# Arduino_SLVN.net
KiCad netlist of a schematic drawn in Altium Designer
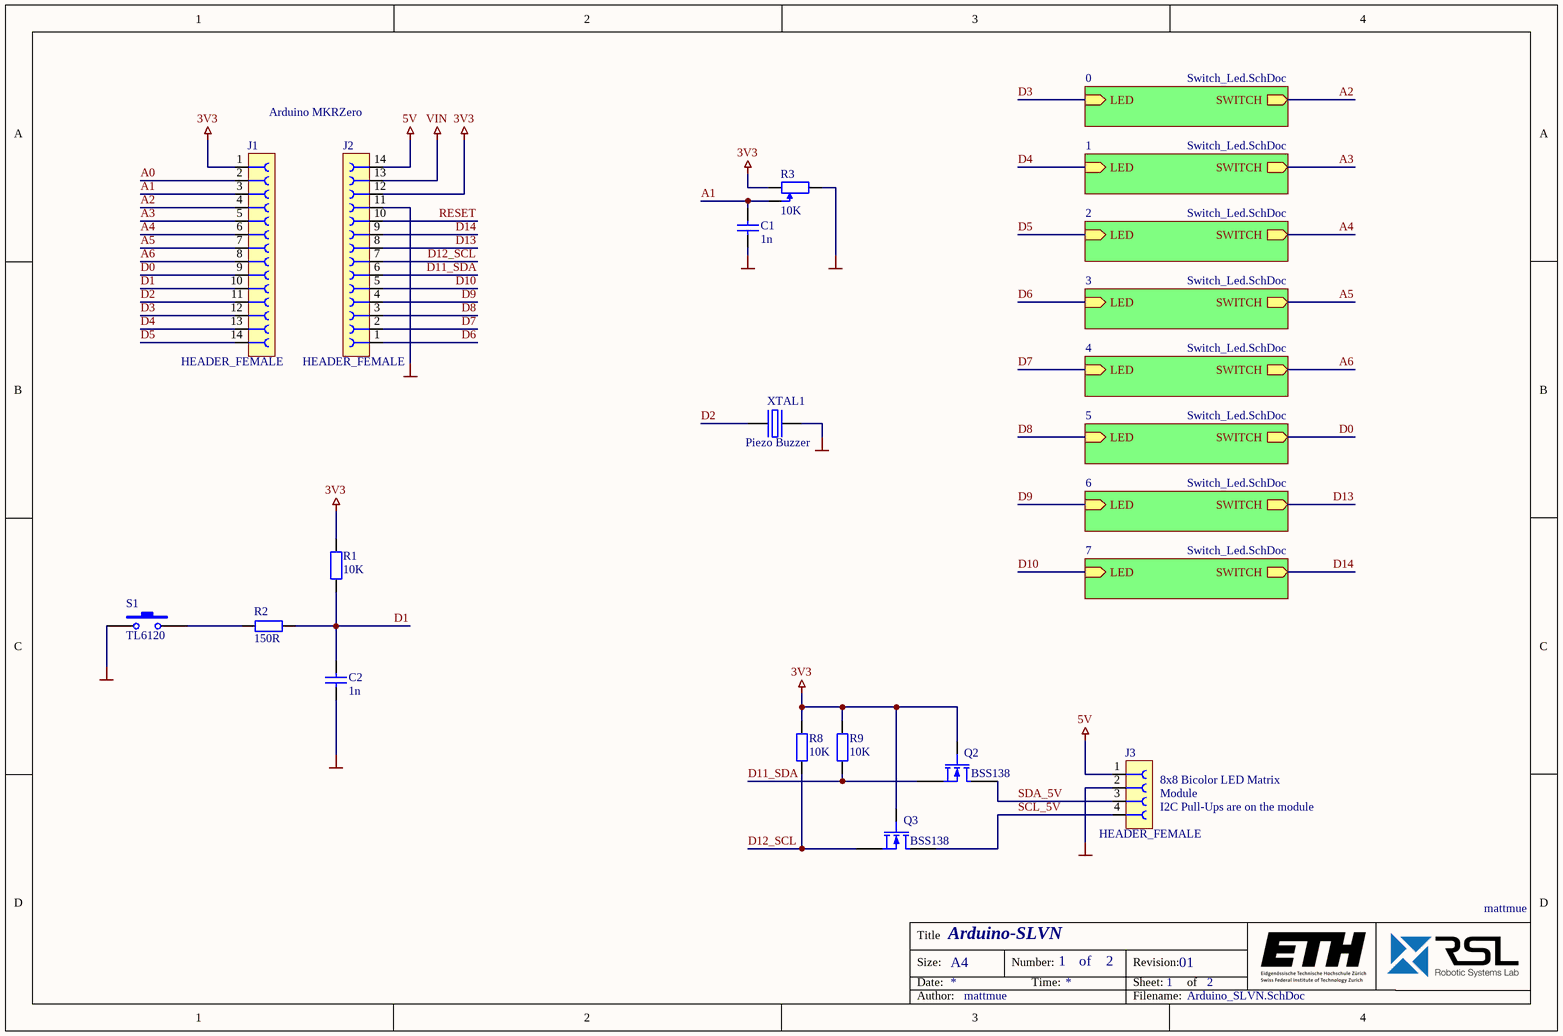
[diagram p0: Arduino_SLVN.SchDoc]

(export (version "E")
  (design (tool "Eeschema 10.0.6"))
  (components
    (comp (ref "C1")
      (value "1n")
      (footprint "SMD_CAPC1608X08N")
      (description "CERCAP 1n 100V 1% NP0/C0G 0603")
      (fields
        (field (name "MANUFACTURER") "KEMET")
        (field (name "MANUFACTURER PART NUMBER") "C0603C102F1GAC7867")
      )
      (libsource (lib "ETHZ Vault") (part "Cap"))
    )
    (comp (ref "C2")
      (value "1n")
      (footprint "SMD_CAPC1608X08N")
      (description "CERCAP 1n 100V 1% NP0/C0G 0603")
      (fields
        (field (name "MANUFACTURER") "KEMET")
        (field (name "MANUFACTURER PART NUMBER") "C0603C102F1GAC7867")
      )
      (libsource (lib "ETHZ Vault") (part "Cap"))
    )
    (comp (ref "J1")
      (value "HEADER_FEMALE")
      (footprint "THT_CONN_1x14_FEMALE_2.54")
      (description "CONN Female 1x14 2.54mm Straight THT 2.54x35.6mm")
      (fields
        (field (name "MANUFACTURER") "Sullins Connector Solutions")
        (field (name "MANUFACTURER PART NUMBER") "PPTC141LFBN-RC")
      )
      (libsource (lib "ETHZ Vault") (part "CON 14x1 Female"))
    )
    (comp (ref "J2")
      (value "HEADER_FEMALE")
      (footprint "THT_CONN_1x14_FEMALE_2.54")
      (description "CONN Female 1x14 2.54mm Straight THT 2.54x35.6mm")
      (fields
        (field (name "MANUFACTURER") "Sullins Connector Solutions")
        (field (name "MANUFACTURER PART NUMBER") "PPTC141LFBN-RC")
      )
      (libsource (lib "") (part "CON 14x1 Female_1"))
    )
    (comp (ref "J3")
      (value "HEADER_FEMALE")
      (footprint "THT_CONN_1x4_FEMALE_2.54")
      (description "CONN Female 1x4 2.54mm Straight THT 2.54x10.16mm")
      (fields
        (field (name "MANUFACTURER") "Sullins Connector Solutions")
        (field (name "MANUFACTURER PART NUMBER") "PPTC041LFBN-RC")
      )
      (libsource (lib "ETHZ Vault") (part "CON 4x1 Female"))
    )
    (comp (ref "Q2")
      (value "BSS138")
      (footprint "SOT323 SC70")
      (description "MOSFET N 0.2A 50V SOT323")
      (fields
        (field (name "MANUFACTURER2 PART NUMBER") "BSS138W-TP")
        (field (name "MANUFACTURER") "Diodes Incorporated")
      )
      (libsource (lib "ETHZ Vault") (part "MOSFET-N"))
    )
    (comp (ref "Q3")
      (value "BSS138")
      (footprint "SOT323 SC70")
      (description "MOSFET N 0.2A 50V SOT323")
      (fields
        (field (name "MANUFACTURER2 PART NUMBER") "BSS138W-TP")
        (field (name "MANUFACTURER") "Diodes Incorporated")
      )
      (libsource (lib "ETHZ Vault") (part "MOSFET-N"))
    )
    (comp (ref "R1")
      (value "10K")
      (footprint "SMD_RESC1608X05N")
      (description "RES 10K 100mW 1% 0603")
      (fields
        (field (name "MANUFACTURER") "YAEGO")
        (field (name "MANUFACTURER PART NUMBER") "RC0603FR-0710KL")
      )
      (libsource (lib "ETHZ Vault") (part "Res"))
    )
    (comp (ref "R2")
      (value "150R")
      (footprint "SMD_RESC1608X05N")
      (description "RES 150R 100mW 1% 0603")
      (fields
        (field (name "MANUFACTURER") "YAEGO")
        (field (name "MANUFACTURER PART NUMBER") "RC0603FR-07150RL")
      )
      (libsource (lib "ETHZ Vault") (part "Res"))
    )
    (comp (ref "R3")
      (value "10K")
      (footprint "THT_PTV09A-1")
      (description "POTENTIOMETER 10K 50mW 20% 11x9.7mm")
      (fields
        (field (name "MANUFACTURER") "Bourns Inc.")
        (field (name "MANUFACTURER PART NUMBER") "PTV09A-4020S-B103")
      )
      (libsource (lib "ETHZ Vault") (part "Res poti"))
    )
    (comp (ref "R8")
      (value "10K")
      (footprint "SMD_RESC1608X05N")
      (description "RES 10K 100mW 1% 0603")
      (fields
        (field (name "MANUFACTURER") "YAEGO")
        (field (name "MANUFACTURER PART NUMBER") "RC0603FR-0710KL")
      )
      (libsource (lib "ETHZ Vault") (part "Res"))
    )
    (comp (ref "R9")
      (value "10K")
      (footprint "SMD_RESC1608X05N")
      (description "RES 10K 100mW 1% 0603")
      (fields
        (field (name "MANUFACTURER") "YAEGO")
        (field (name "MANUFACTURER PART NUMBER") "RC0603FR-0710KL")
      )
      (libsource (lib "ETHZ Vault") (part "Res"))
    )
    (comp (ref "S1")
      (value "TL6120")
      (footprint "SMD_TL6120")
      (description "BUTTON SPST 12V 0.05A 7.4x7.4mm")
      (fields
        (field (name "MANUFACTURER") "E-Switch")
        (field (name "MANUFACTURER PART NUMBER") "TL6120CF300QG")
      )
      (libsource (lib "ETHZ Vault") (part "SW PB"))
    )
    (comp (ref "sdfg1")
      (value "Mattmue-Logo")
      (footprint "GRAPH_MATTMUE_6MM")
      (description "GRAPH MATTMUE")
      (libsource (lib "ETHZ Vault") (part "Mattmue"))
    )
    (comp (ref "XTAL1")
      (value "PS1240P02BT")
      (footprint "THT_PIEZO_5mm")
      (description "PASSIVE PIEZO_BUZZER 12.6x7.8mm")
      (fields (field (name "MANUFACTURER") "TDK Corporation") (field (name "NOTE") "Piezo Buzzer"))
      (libsource (lib "ETHZ Vault") (part "XTAL_2P"))
    )
  )
  (nets
    (net (code "1") (name "/A0") (class "Default")
      (node (ref "J1") (pin "2") (pinfunction "2_2") (pintype "passive"))
    )
    (net (code "2") (name "/A1") (class "Default")
      (node (ref "C1") (pin "2") (pinfunction "2_2") (pintype "passive"))
      (node (ref "J1") (pin "3") (pinfunction "3_3") (pintype "passive"))
      (node (ref "R3") (pin "3") (pinfunction "TAP_3") (pintype "passive"))
    )
    (net (code "3") (name "/A2") (class "Default")
      (node (ref "J1") (pin "4") (pinfunction "4_4") (pintype "passive"))
    )
    (net (code "4") (name "/A3") (class "Default")
      (node (ref "J1") (pin "5") (pinfunction "5_5") (pintype "passive"))
    )
    (net (code "5") (name "/A4") (class "Default")
      (node (ref "J1") (pin "6") (pinfunction "6_6") (pintype "passive"))
    )
    (net (code "6") (name "/A5") (class "Default")
      (node (ref "J1") (pin "7") (pinfunction "7_7") (pintype "passive"))
    )
    (net (code "7") (name "/A6") (class "Default")
      (node (ref "J1") (pin "8") (pinfunction "8_8") (pintype "passive"))
    )
    (net (code "8") (name "/D0") (class "Default")
      (node (ref "J1") (pin "9") (pinfunction "9_9") (pintype "passive"))
    )
    (net (code "9") (name "/D1") (class "Default")
      (node (ref "C2") (pin "2") (pinfunction "2_2") (pintype "passive"))
      (node (ref "J1") (pin "10") (pinfunction "10_10") (pintype "passive"))
      (node (ref "R1") (pin "1") (pinfunction "1_1") (pintype "passive"))
      (node (ref "R2") (pin "1") (pinfunction "1_1") (pintype "passive"))
    )
    (net (code "10") (name "/D2") (class "Default")
      (node (ref "J1") (pin "11") (pinfunction "11_11") (pintype "passive"))
      (node (ref "XTAL1") (pin "1") (pinfunction "1_1") (pintype "passive"))
    )
    (net (code "11") (name "/D3") (class "Default")
      (node (ref "J1") (pin "12") (pinfunction "12_12") (pintype "passive"))
    )
    (net (code "12") (name "/D4") (class "Default")
      (node (ref "J1") (pin "13") (pinfunction "13_13") (pintype "passive"))
    )
    (net (code "13") (name "/D5") (class "Default")
      (node (ref "J1") (pin "14") (pinfunction "14_14") (pintype "passive"))
    )
    (net (code "14") (name "/D6") (class "Default")
      (node (ref "J2") (pin "1") (pinfunction "1_1") (pintype "passive"))
    )
    (net (code "15") (name "/D7") (class "Default")
      (node (ref "J2") (pin "2") (pinfunction "2_2") (pintype "passive"))
    )
    (net (code "16") (name "/D8") (class "Default")
      (node (ref "J2") (pin "3") (pinfunction "3_3") (pintype "passive"))
    )
    (net (code "17") (name "/D9") (class "Default")
      (node (ref "J2") (pin "4") (pinfunction "4_4") (pintype "passive"))
    )
    (net (code "18") (name "/D10") (class "Default")
      (node (ref "J2") (pin "5") (pinfunction "5_5") (pintype "passive"))
    )
    (net (code "19") (name "/D11_SDA") (class "Default")
      (node (ref "J2") (pin "6") (pinfunction "6_6") (pintype "passive"))
      (node (ref "Q2") (pin "2") (pinfunction "S_2") (pintype "passive"))
      (node (ref "R9") (pin "1") (pinfunction "1_1") (pintype "passive"))
    )
    (net (code "20") (name "/D12_SCL") (class "Default")
      (node (ref "J2") (pin "7") (pinfunction "7_7") (pintype "passive"))
      (node (ref "Q3") (pin "2") (pinfunction "S_2") (pintype "passive"))
      (node (ref "R8") (pin "1") (pinfunction "1_1") (pintype "passive"))
    )
    (net (code "21") (name "/D13") (class "Default")
      (node (ref "J2") (pin "8") (pinfunction "8_8") (pintype "passive"))
    )
    (net (code "22") (name "/D14") (class "Default")
      (node (ref "J2") (pin "9") (pinfunction "9_9") (pintype "passive"))
    )
    (net (code "23") (name "/RESET") (class "Default")
      (node (ref "J2") (pin "10") (pinfunction "10_10") (pintype "passive"))
    )
    (net (code "24") (name "/SCL_5V") (class "Default")
      (node (ref "J3") (pin "4") (pinfunction "4_4") (pintype "passive"))
      (node (ref "Q3") (pin "3") (pinfunction "D_3") (pintype "passive"))
    )
    (net (code "25") (name "/SDA_5V") (class "Default")
      (node (ref "J3") (pin "3") (pinfunction "3_3") (pintype "passive"))
      (node (ref "Q2") (pin "3") (pinfunction "D_3") (pintype "passive"))
    )
    (net (code "26") (name "3V3") (class "Default")
      (node (ref "J1") (pin "1") (pinfunction "1_1") (pintype "passive"))
      (node (ref "J2") (pin "12") (pinfunction "12_12") (pintype "passive"))
      (node (ref "Q2") (pin "1") (pinfunction "G_1") (pintype "passive"))
      (node (ref "Q3") (pin "1") (pinfunction "G_1") (pintype "passive"))
      (node (ref "R1") (pin "2") (pinfunction "2_2") (pintype "passive"))
      (node (ref "R3") (pin "1") (pinfunction "1_1") (pintype "passive"))
      (node (ref "R8") (pin "2") (pinfunction "2_2") (pintype "passive"))
      (node (ref "R9") (pin "2") (pinfunction "2_2") (pintype "passive"))
    )
    (net (code "27") (name "5V") (class "Default")
      (node (ref "J2") (pin "14") (pinfunction "14_14") (pintype "passive"))
      (node (ref "J3") (pin "1") (pinfunction "1_1") (pintype "passive"))
    )
    (net (code "28") (name "GND") (class "Default")
      (node (ref "C1") (pin "1") (pinfunction "1_1") (pintype "passive"))
      (node (ref "C2") (pin "1") (pinfunction "1_1") (pintype "passive"))
      (node (ref "J2") (pin "11") (pinfunction "11_11") (pintype "passive"))
      (node (ref "J3") (pin "2") (pinfunction "2_2") (pintype "passive"))
      (node (ref "R3") (pin "2") (pinfunction "2_2") (pintype "passive"))
      (node (ref "S1") (pin "1") (pinfunction "1_1") (pintype "passive"))
      (node (ref "XTAL1") (pin "2") (pinfunction "2_2") (pintype "passive"))
    )
    (net (code "29") (name "Net-(R2-Pad2)") (class "Default")
      (node (ref "R2") (pin "2") (pinfunction "2_2") (pintype "passive"))
      (node (ref "S1") (pin "2") (pinfunction "2_2") (pintype "passive"))
    )
    (net (code "30") (name "VIN") (class "Default")
      (node (ref "J2") (pin "13") (pinfunction "13_13") (pintype "passive"))
    )
  )
)
